# CurrentMeter2.net
KiCad netlist of a schematic drawn in EAGLE
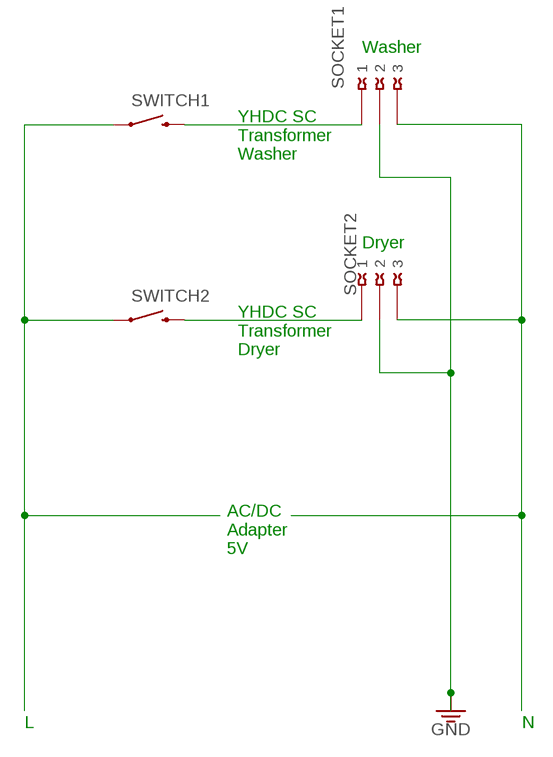
[diagram p0: schematic, sheet 1]

(export (version "E")
  (design (tool "Eeschema 10.0.6"))
  (components
    (comp (ref "SOCKET1")
      (value "009175003")
      (footprint "eagle-import:009175003")
      (fields (field (name "MPN") "009175003001006"))
      (libsource (lib "eagle-import") (part "009175003"))
    )
    (comp (ref "SOCKET2")
      (value "009175003")
      (footprint "eagle-import:009175003")
      (fields (field (name "MPN") "009175003001006"))
      (libsource (lib "eagle-import") (part "009175003"))
    )
    (comp (ref "SWITCH1")
      (value "RS032G05A3SM-SPST-MOMENTARY-SWSMD-1101NE")
      (footprint "eagle-import:TACTILE-SWITCH-1101NE")
      (libsource (lib "eagle-import") (part "RS032G05A3SM-SPST-MOMENTARY-SWSMD-1101NE"))
    )
    (comp (ref "SWITCH2")
      (value "RS032G05A3SM-SPST-MOMENTARY-SWSMD-1101NE")
      (footprint "eagle-import:TACTILE-SWITCH-1101NE")
      (libsource (lib "eagle-import") (part "RS032G05A3SM-SPST-MOMENTARY-SWSMD-1101NE"))
    )
  )
  (nets
    (net (code "1") (name "GND") (class "Default")
      (node (ref "SOCKET1") (pin "2@1") (pinfunction "2_2@1") (pintype "passive"))
      (node (ref "SOCKET2") (pin "2@1") (pinfunction "2_2@1") (pintype "passive"))
    )
    (net (code "2") (name "Net-(SOCKET1-1-Pad1@1)") (class "Default")
      (node (ref "SOCKET1") (pin "1@1") (pinfunction "1_1@1") (pintype "passive"))
      (node (ref "SWITCH1") (pin "2") (pinfunction "2_2") (pintype "passive"))
    )
    (net (code "3") (name "Net-(SOCKET1-3-Pad3@2)") (class "Default")
      (node (ref "SOCKET1") (pin "3@2") (pinfunction "3_3@2") (pintype "passive"))
      (node (ref "SOCKET2") (pin "3@2") (pinfunction "3_3@2") (pintype "passive"))
    )
    (net (code "4") (name "Net-(SOCKET2-1-Pad1@1)") (class "Default")
      (node (ref "SOCKET2") (pin "1@1") (pinfunction "1_1@1") (pintype "passive"))
      (node (ref "SWITCH2") (pin "2") (pinfunction "2_2") (pintype "passive"))
    )
    (net (code "5") (name "Net-(SWITCH1-Pad1)") (class "Default")
      (node (ref "SWITCH1") (pin "1") (pinfunction "1_1") (pintype "passive"))
      (node (ref "SWITCH2") (pin "1") (pinfunction "1_1") (pintype "passive"))
    )
    (net (code "6") (name "unconnected-(SOCKET1-Pad1)") (class "Default")
      (node (ref "SOCKET1") (pin "1") (pinfunction "1_1") (pintype "passive"))
    )
    (net (code "7") (name "unconnected-(SOCKET1-Pad2)") (class "Default")
      (node (ref "SOCKET1") (pin "2") (pinfunction "2_2") (pintype "passive"))
    )
    (net (code "8") (name "unconnected-(SOCKET1-Pad3)") (class "Default")
      (node (ref "SOCKET1") (pin "3") (pinfunction "3_3") (pintype "passive"))
    )
    (net (code "9") (name "unconnected-(SOCKET2-Pad1)") (class "Default")
      (node (ref "SOCKET2") (pin "1") (pinfunction "1_1") (pintype "passive"))
    )
    (net (code "10") (name "unconnected-(SOCKET2-Pad2)") (class "Default")
      (node (ref "SOCKET2") (pin "2") (pinfunction "2_2") (pintype "passive"))
    )
    (net (code "11") (name "unconnected-(SOCKET2-Pad3)") (class "Default")
      (node (ref "SOCKET2") (pin "3") (pinfunction "3_3") (pintype "passive"))
    )
  )
)
